# ADC_Circuit.net
KiCad netlist of a schematic drawn in Altium Designer
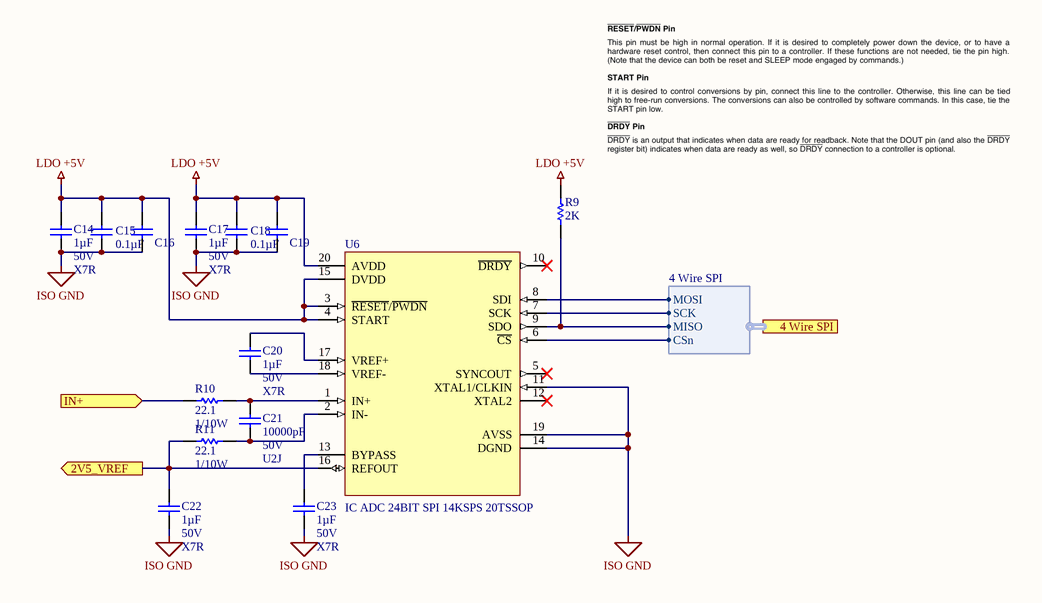
[diagram p0: ADC_Circuit.SchDoc]

(export (version "E")
  (design (tool "Eeschema 10.0.6"))
  (components
    (comp (ref "C14")
      (value "CAP CER 1UF 50V 10% X7R 0603")
      (footprint "CAP, 0603")
      (description "1µF ±10% 50V Ceramic Capacitor X7R 0603 (1608 Metric)")
      (fields
        (field (name "TOLERANCE") "±10%")
        (field (name "CAPACITANCE") "1µF")
        (field (name "VOLTAGE") "50V")
        (field (name "TEMPERATURE COEFFICIENT") "X7R")
      )
      (libsource (lib "Schematic Diagrams") (part "CAP CER 1UF 50V 10% X7R 0603"))
    )
    (comp (ref "C15")
      (value "CAP CER 0.1UF 50V 10% X7R 0603")
      (footprint "CAP, 0603")
      (description "0.10µF ±10% 50V Ceramic Capacitor X7R 0603 (1608 Metric)")
      (fields
        (field (name "TOLERANCE") "±10%")
        (field (name "CAPACITANCE") "0.1µF")
        (field (name "VOLTAGE") "50V")
      )
      (libsource (lib "Schematic Diagrams") (part "CAP CER 0.1UF 50V 10% X7R 0603"))
    )
    (comp (ref "C16")
      (value "CAP CER 0.022UF 50V 10% X7R 0603")
      (footprint "CAP, 0603")
      (description "0.022µF ±10% 50V Ceramic Capacitor X7R 0603 (1608 Metric)")
      (fields (field (name "TOLERANCE") "±10%"))
      (libsource (lib "Schematic Diagrams") (part "CAP CER 0.022UF 50V 10% X7R 0603"))
    )
    (comp (ref "C17")
      (value "CAP CER 1UF 50V 10% X7R 0603")
      (footprint "CAP, 0603")
      (description "1µF ±10% 50V Ceramic Capacitor X7R 0603 (1608 Metric)")
      (fields
        (field (name "TOLERANCE") "±10%")
        (field (name "CAPACITANCE") "1µF")
        (field (name "VOLTAGE") "50V")
        (field (name "TEMPERATURE COEFFICIENT") "X7R")
      )
      (libsource (lib "Schematic Diagrams") (part "CAP CER 1UF 50V 10% X7R 0603"))
    )
    (comp (ref "C18")
      (value "CAP CER 0.1UF 50V 10% X7R 0603")
      (footprint "CAP, 0603")
      (description "0.10µF ±10% 50V Ceramic Capacitor X7R 0603 (1608 Metric)")
      (fields
        (field (name "TOLERANCE") "±10%")
        (field (name "CAPACITANCE") "0.1µF")
        (field (name "VOLTAGE") "50V")
      )
      (libsource (lib "Schematic Diagrams") (part "CAP CER 0.1UF 50V 10% X7R 0603"))
    )
    (comp (ref "C19")
      (value "CAP CER 0.022UF 50V 10% X7R 0603")
      (footprint "CAP, 0603")
      (description "0.022µF ±10% 50V Ceramic Capacitor X7R 0603 (1608 Metric)")
      (fields (field (name "TOLERANCE") "±10%"))
      (libsource (lib "Schematic Diagrams") (part "CAP CER 0.022UF 50V 10% X7R 0603"))
    )
    (comp (ref "C20")
      (value "CAP CER 1UF 50V 10% X7R 0603")
      (footprint "CAP, 0603")
      (description "1µF ±10% 50V Ceramic Capacitor X7R 0603 (1608 Metric)")
      (fields
        (field (name "TOLERANCE") "±10%")
        (field (name "CAPACITANCE") "1µF")
        (field (name "VOLTAGE") "50V")
        (field (name "TEMPERATURE COEFFICIENT") "X7R")
      )
      (libsource (lib "Schematic Diagrams") (part "CAP CER 1UF 50V 10% X7R 0603"))
    )
    (comp (ref "C21")
      (value "CAP CER 10nF 50V 5% X7R 0603")
      (footprint "CAP, 0603")
      (description "10000pF ±5% 50V Ceramic Capacitor U2J 0603 (1608 Metric)")
      (fields
        (field (name "TOLERANCE") "±5%")
        (field (name "CAPACITANCE") "10000pF")
        (field (name "VOLTAGE") "50V")
        (field (name "TEMPERATURE COEFFICIENT") "U2J")
      )
      (libsource (lib "Schematic Diagrams") (part "CAP CER 10nF 50V 5% X7R 0603"))
    )
    (comp (ref "C22")
      (value "CAP CER 1UF 50V 10% X7R 0603")
      (footprint "CAP, 0603")
      (description "1µF ±10% 50V Ceramic Capacitor X7R 0603 (1608 Metric)")
      (fields
        (field (name "TOLERANCE") "±10%")
        (field (name "CAPACITANCE") "1µF")
        (field (name "VOLTAGE") "50V")
        (field (name "TEMPERATURE COEFFICIENT") "X7R")
      )
      (libsource (lib "Schematic Diagrams") (part "CAP CER 1UF 50V 10% X7R 0603"))
    )
    (comp (ref "C23")
      (value "CAP CER 1UF 50V 10% X7R 0603")
      (footprint "CAP, 0603")
      (description "1µF ±10% 50V Ceramic Capacitor X7R 0603 (1608 Metric)")
      (fields
        (field (name "TOLERANCE") "±10%")
        (field (name "CAPACITANCE") "1µF")
        (field (name "VOLTAGE") "50V")
        (field (name "TEMPERATURE COEFFICIENT") "X7R")
      )
      (libsource (lib "Schematic Diagrams") (part "CAP CER 1UF 50V 10% X7R 0603"))
    )
    (comp (ref "R9")
      (value "2K")
      (footprint "RES, 0603")
      (description "2k Ohm ±1% 0.1W, 1/10W Chip Resistor 0603 (1608 Metric) Moisture Resistant Thick Film")
      (fields
        (field (name "MANUFACTURER") "Yageo")
        (field (name "MANUFACTURER PART NUMBER") "RC0603FR-072KL")
      )
      (libsource (lib "Schematic Diagrams") (part "RES 2K OHM 1% 1/10W 0603"))
    )
    (comp (ref "R10")
      (value "RES 22.1 OHM 1% 1/10W 0603")
      (footprint "RES, 0603")
      (description "22.1 Ohm ±1% 0.1W, 1/10W Chip Resistor 0603 (1608 Metric) Moisture Resistant Thick Film")
      (fields
        (field (name "TOLERANCE") "±1%")
        (field (name "RESISTANCE") "22.1")
        (field (name "POWER") "1/10W")
      )
      (libsource (lib "Schematic Diagrams") (part "RES 22.1 OHM 1% 1/10W 0603"))
    )
    (comp (ref "R11")
      (value "RES 22.1 OHM 1% 1/10W 0603")
      (footprint "RES, 0603")
      (description "22.1 Ohm ±1% 0.1W, 1/10W Chip Resistor 0603 (1608 Metric) Moisture Resistant Thick Film")
      (fields
        (field (name "TOLERANCE") "±1%")
        (field (name "RESISTANCE") "22.1")
        (field (name "POWER") "1/10W")
      )
      (libsource (lib "Schematic Diagrams") (part "RES 22.1 OHM 1% 1/10W 0603"))
    )
    (comp (ref "U6")
      (value "IC ADC 24BIT SPI 14KSPS 20TSSOP")
      (footprint "TSSOP65P640X120-20N")
      (description "24 Bit Analog to Digital Converter 1 Input 1 Sigma-Delta 20-TSSOP")
      (libsource (lib "Schematic Diagrams") (part "IC ADC 24BIT SPI 14KSPS 20TSSOP"))
    )
  )
  (nets
    (net (code "4") (name "/2V5_VREF") (class "Default")
      (node (ref "C22") (pin "1") (pinfunction "1_1") (pintype "passive"))
      (node (ref "R11") (pin "1") (pinfunction "1_1") (pintype "passive"))
      (node (ref "U6") (pin "16") (pinfunction "REFOUT_16") (pintype "bidirectional"))
    )
    (net (code "5") (name "/CSn") (class "Default")
      (node (ref "U6") (pin "6") (pinfunction "~{CS}_6") (pintype "input"))
    )
    (net (code "6") (name "/IN+") (class "Default")
      (node (ref "R10") (pin "1") (pinfunction "1_1") (pintype "passive"))
    )
    (net (code "7") (name "/MISO") (class "Default")
      (node (ref "R9") (pin "2") (pinfunction "2_2") (pintype "passive"))
      (node (ref "U6") (pin "9") (pinfunction "SDO_9") (pintype "output"))
    )
    (net (code "8") (name "/MOSI") (class "Default")
      (node (ref "U6") (pin "8") (pinfunction "SDI_8") (pintype "input"))
    )
    (net (code "9") (name "/SCK") (class "Default")
      (node (ref "U6") (pin "7") (pinfunction "SCK_7") (pintype "input"))
    )
    (net (code "11") (name "ISO GND") (class "Default")
      (node (ref "C14") (pin "2") (pinfunction "2_2") (pintype "passive"))
      (node (ref "C15") (pin "2") (pinfunction "2_2") (pintype "passive"))
      (node (ref "C16") (pin "2") (pinfunction "2_2") (pintype "passive"))
      (node (ref "C17") (pin "2") (pinfunction "2_2") (pintype "passive"))
      (node (ref "C18") (pin "2") (pinfunction "2_2") (pintype "passive"))
      (node (ref "C19") (pin "2") (pinfunction "2_2") (pintype "passive"))
      (node (ref "C22") (pin "2") (pinfunction "2_2") (pintype "passive"))
      (node (ref "C23") (pin "2") (pinfunction "2_2") (pintype "passive"))
      (node (ref "U6") (pin "11") (pinfunction "XTAL1/CLKIN_11") (pintype "input"))
      (node (ref "U6") (pin "14") (pinfunction "DGND_14") (pintype "passive"))
      (node (ref "U6") (pin "19") (pinfunction "AVSS_19") (pintype "passive"))
    )
    (net (code "12") (name "LDO +5V") (class "Default")
      (node (ref "C14") (pin "1") (pinfunction "1_1") (pintype "passive"))
      (node (ref "C15") (pin "1") (pinfunction "1_1") (pintype "passive"))
      (node (ref "C16") (pin "1") (pinfunction "1_1") (pintype "passive"))
      (node (ref "C17") (pin "1") (pinfunction "1_1") (pintype "passive"))
      (node (ref "C18") (pin "1") (pinfunction "1_1") (pintype "passive"))
      (node (ref "C19") (pin "1") (pinfunction "1_1") (pintype "passive"))
      (node (ref "R9") (pin "1") (pinfunction "1_1") (pintype "passive"))
      (node (ref "U6") (pin "15") (pinfunction "DVDD_15") (pintype "passive"))
      (node (ref "U6") (pin "20") (pinfunction "AVDD_20") (pintype "passive"))
      (node (ref "U6") (pin "3") (pinfunction "~{RESET}/~{PWDN}_3") (pintype "input"))
      (node (ref "U6") (pin "4") (pinfunction "START_4") (pintype "input"))
    )
    (net (code "13") (name "Net-(U6-BYPASS)") (class "Default")
      (node (ref "C23") (pin "1") (pinfunction "1_1") (pintype "passive"))
      (node (ref "U6") (pin "13") (pinfunction "BYPASS_13") (pintype "passive"))
    )
    (net (code "14") (name "Net-(U6-IN+)") (class "Default")
      (node (ref "C21") (pin "1") (pinfunction "1_1") (pintype "passive"))
      (node (ref "R10") (pin "2") (pinfunction "2_2") (pintype "passive"))
      (node (ref "U6") (pin "1") (pinfunction "IN+_1") (pintype "input"))
    )
    (net (code "15") (name "Net-(U6-IN-)") (class "Default")
      (node (ref "C21") (pin "2") (pinfunction "2_2") (pintype "passive"))
      (node (ref "R11") (pin "2") (pinfunction "2_2") (pintype "passive"))
      (node (ref "U6") (pin "2") (pinfunction "IN-_2") (pintype "input"))
    )
    (net (code "16") (name "Net-(U6-VREF+)") (class "Default")
      (node (ref "C20") (pin "1") (pinfunction "1_1") (pintype "passive"))
      (node (ref "U6") (pin "17") (pinfunction "VREF+_17") (pintype "input"))
    )
    (net (code "17") (name "Net-(U6-VREF-)") (class "Default")
      (node (ref "C20") (pin "2") (pinfunction "2_2") (pintype "passive"))
      (node (ref "U6") (pin "18") (pinfunction "VREF-_18") (pintype "input"))
    )
    (net (code "18") (name "unconnected-(U6-SYNCOUT-Pad5)") (class "Default")
      (node (ref "U6") (pin "5") (pinfunction "SYNCOUT_5") (pintype "output+no_connect"))
    )
    (net (code "19") (name "unconnected-(U6-XTAL2-Pad12)") (class "Default")
      (node (ref "U6") (pin "12") (pinfunction "XTAL2_12") (pintype "passive+no_connect"))
    )
    (net (code "20") (name "unconnected-(U6-~{DRDY}-Pad10)") (class "Default")
      (node (ref "U6") (pin "10") (pinfunction "~{DRDY}_10") (pintype "output+no_connect"))
    )
  )
)
